# Sheet1.net
KiCad netlist of a schematic drawn in Altium Designer
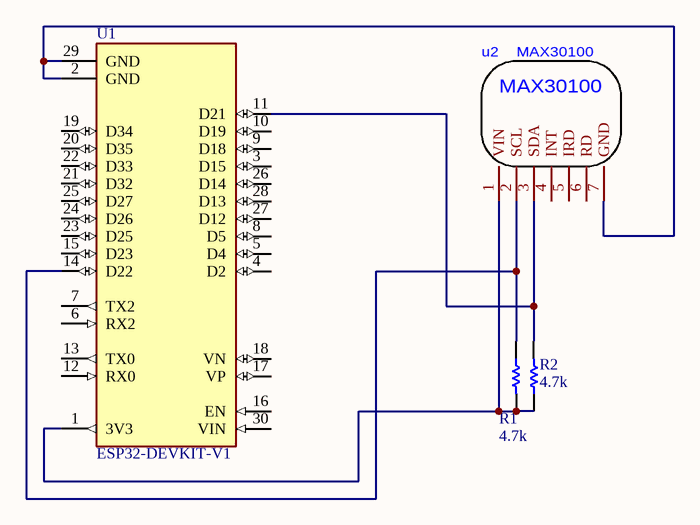
[diagram p0: Sheet1.SchDoc]

(export (version "E")
  (design (tool "Eeschema 10.0.6"))
  (components
    (comp (ref "R1")
      (value "4.7k")
      (footprint "R1/4W")
      (description "Resistor")
      (fields
        (field (name "MANUFACTURER") "Generic Components")
        (field (name "Comment") "Res1")
        (field (name "PUBLISHER") "Altium Hobart Technology Centre")
      )
      (libsource (lib "syhaunguyen") (part "Res1_1"))
    )
    (comp (ref "R2")
      (value "4.7k")
      (footprint "R1/4W")
      (description "Resistor")
      (fields
        (field (name "MANUFACTURER") "Generic Components")
        (field (name "Comment") "Res1")
        (field (name "PUBLISHER") "Altium Hobart Technology Centre")
      )
      (libsource (lib "syhaunguyen") (part "Res1_1"))
    )
    (comp (ref "U1")
      (value "ESP32-DEVKIT-V1")
      (footprint "MODULE_ESP32_DEVKIT_V1")
      (fields (field (name "MF") "Do it"))
      (libsource (lib "ESP32-DEVKIT-V1") (part "ESP32-DEVKIT-V1"))
    )
    (comp (ref "u2")
      (value "MAX30100")
      (footprint "MAX30100_MODULE")
      (libsource (lib "max30100sch") (part "MAX30100 MODULE COPY"))
    )
  )
  (nets
    (net (code "1") (name "Net-(U1-3V3)") (class "Default")
      (node (ref "R1") (pin "2") (pinfunction "2_2") (pintype "passive"))
      (node (ref "R2") (pin "1") (pinfunction "1_1") (pintype "passive"))
      (node (ref "U1") (pin "1") (pinfunction "3V3_1") (pintype "output"))
      (node (ref "u2") (pin "1") (pinfunction "VIN_1") (pintype "passive"))
    )
    (net (code "2") (name "Net-(U1-D21)") (class "Default")
      (node (ref "R2") (pin "2") (pinfunction "2_2") (pintype "passive"))
      (node (ref "U1") (pin "11") (pinfunction "D21_11") (pintype "bidirectional"))
      (node (ref "u2") (pin "3") (pinfunction "SDA_3") (pintype "passive"))
    )
    (net (code "3") (name "Net-(U1-D22)") (class "Default")
      (node (ref "R1") (pin "1") (pinfunction "1_1") (pintype "passive"))
      (node (ref "U1") (pin "14") (pinfunction "D22_14") (pintype "bidirectional"))
      (node (ref "u2") (pin "2") (pinfunction "SCL_2") (pintype "passive"))
    )
    (net (code "4") (name "Net-(u2-GND)") (class "Default")
      (node (ref "U1") (pin "2") (pinfunction "GND_2") (pintype "power_in"))
      (node (ref "U1") (pin "29") (pinfunction "GND_29") (pintype "power_in"))
      (node (ref "u2") (pin "7") (pinfunction "GND_7") (pintype "passive"))
    )
    (net (code "5") (name "unconnected-(U1-D2-Pad4)") (class "Default")
      (node (ref "U1") (pin "4") (pinfunction "D2_4") (pintype "bidirectional"))
    )
    (net (code "6") (name "unconnected-(U1-D4-Pad5)") (class "Default")
      (node (ref "U1") (pin "5") (pinfunction "D4_5") (pintype "bidirectional"))
    )
    (net (code "7") (name "unconnected-(U1-D5-Pad8)") (class "Default")
      (node (ref "U1") (pin "8") (pinfunction "D5_8") (pintype "bidirectional"))
    )
    (net (code "8") (name "unconnected-(U1-D12-Pad27)") (class "Default")
      (node (ref "U1") (pin "27") (pinfunction "D12_27") (pintype "bidirectional"))
    )
    (net (code "9") (name "unconnected-(U1-D13-Pad28)") (class "Default")
      (node (ref "U1") (pin "28") (pinfunction "D13_28") (pintype "bidirectional"))
    )
    (net (code "10") (name "unconnected-(U1-D14-Pad26)") (class "Default")
      (node (ref "U1") (pin "26") (pinfunction "D14_26") (pintype "bidirectional"))
    )
    (net (code "11") (name "unconnected-(U1-D15-Pad3)") (class "Default")
      (node (ref "U1") (pin "3") (pinfunction "D15_3") (pintype "bidirectional"))
    )
    (net (code "12") (name "unconnected-(U1-D18-Pad9)") (class "Default")
      (node (ref "U1") (pin "9") (pinfunction "D18_9") (pintype "bidirectional"))
    )
    (net (code "13") (name "unconnected-(U1-D19-Pad10)") (class "Default")
      (node (ref "U1") (pin "10") (pinfunction "D19_10") (pintype "bidirectional"))
    )
    (net (code "14") (name "unconnected-(U1-D23-Pad15)") (class "Default")
      (node (ref "U1") (pin "15") (pinfunction "D23_15") (pintype "bidirectional"))
    )
    (net (code "15") (name "unconnected-(U1-D25-Pad23)") (class "Default")
      (node (ref "U1") (pin "23") (pinfunction "D25_23") (pintype "bidirectional"))
    )
    (net (code "16") (name "unconnected-(U1-D26-Pad24)") (class "Default")
      (node (ref "U1") (pin "24") (pinfunction "D26_24") (pintype "bidirectional"))
    )
    (net (code "17") (name "unconnected-(U1-D27-Pad25)") (class "Default")
      (node (ref "U1") (pin "25") (pinfunction "D27_25") (pintype "bidirectional"))
    )
    (net (code "18") (name "unconnected-(U1-D32-Pad21)") (class "Default")
      (node (ref "U1") (pin "21") (pinfunction "D32_21") (pintype "bidirectional"))
    )
    (net (code "19") (name "unconnected-(U1-D33-Pad22)") (class "Default")
      (node (ref "U1") (pin "22") (pinfunction "D33_22") (pintype "bidirectional"))
    )
    (net (code "20") (name "unconnected-(U1-D34-Pad19)") (class "Default")
      (node (ref "U1") (pin "19") (pinfunction "D34_19") (pintype "bidirectional"))
    )
    (net (code "21") (name "unconnected-(U1-D35-Pad20)") (class "Default")
      (node (ref "U1") (pin "20") (pinfunction "D35_20") (pintype "bidirectional"))
    )
    (net (code "22") (name "unconnected-(U1-EN-Pad16)") (class "Default")
      (node (ref "U1") (pin "16") (pinfunction "EN_16") (pintype "input"))
    )
    (net (code "23") (name "unconnected-(U1-RX0-Pad12)") (class "Default")
      (node (ref "U1") (pin "12") (pinfunction "RX0_12") (pintype "input"))
    )
    (net (code "24") (name "unconnected-(U1-RX2-Pad6)") (class "Default")
      (node (ref "U1") (pin "6") (pinfunction "RX2_6") (pintype "input"))
    )
    (net (code "25") (name "unconnected-(U1-TX0-Pad13)") (class "Default")
      (node (ref "U1") (pin "13") (pinfunction "TX0_13") (pintype "output"))
    )
    (net (code "26") (name "unconnected-(U1-TX2-Pad7)") (class "Default")
      (node (ref "U1") (pin "7") (pinfunction "TX2_7") (pintype "output"))
    )
    (net (code "27") (name "unconnected-(U1-VIN-Pad30)") (class "Default")
      (node (ref "U1") (pin "30") (pinfunction "VIN_30") (pintype "input"))
    )
    (net (code "28") (name "unconnected-(U1-VN-Pad18)") (class "Default")
      (node (ref "U1") (pin "18") (pinfunction "VN_18") (pintype "bidirectional"))
    )
    (net (code "29") (name "unconnected-(U1-VP-Pad17)") (class "Default")
      (node (ref "U1") (pin "17") (pinfunction "VP_17") (pintype "bidirectional"))
    )
    (net (code "30") (name "unconnected-(u2-INT-Pad4)") (class "Default")
      (node (ref "u2") (pin "4") (pinfunction "INT_4") (pintype "passive"))
    )
    (net (code "31") (name "unconnected-(u2-IRD-Pad5)") (class "Default")
      (node (ref "u2") (pin "5") (pinfunction "IRD_5") (pintype "passive"))
    )
    (net (code "32") (name "unconnected-(u2-RD-Pad6)") (class "Default")
      (node (ref "u2") (pin "6") (pinfunction "RD_6") (pintype "passive"))
    )
  )
)
